# DB10005_CellNode.net
KiCad netlist of a schematic drawn in Altium Designer
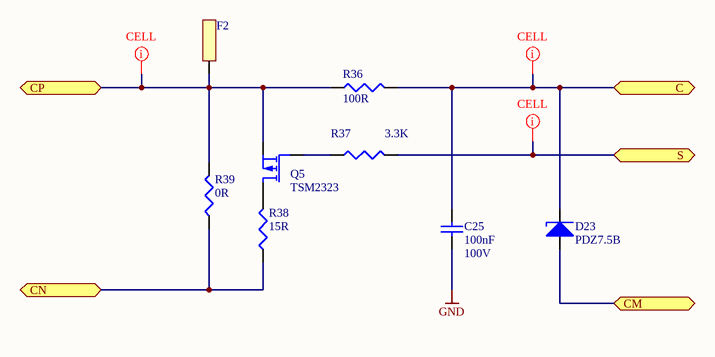
[diagram p0: DB10005_CellNode.SchDoc]

(export (version "E")
  (design (tool "Eeschema 10.0.6"))
  (components
    (comp (ref "C25")
      (value "100nF")
      (footprint "C-0805")
      (description "Capacitor, 100nF, 100V, X7R")
      (fields (field (name "VOLTAGE RATING") "100V"))
      (libsource (lib "AR_Capacitors_Ceramic") (part "100nF/0805/CER/100V"))
    )
    (comp (ref "D23")
      (value "PDZ7.5B")
      (footprint "SOD-323")
      (description "Diode, Vrrm: 7.5V, If: 0.2A, Vf: 0.9V")
      (libsource (lib "AR_Diodes") (part "PDZ7.5B"))
    )
    (comp (ref "F2")
      (value "PCB Fuse")
      (footprint "0603_Fuse_0_2MM")
      (description "Fuse, PCB, 1A, 60V, T:-40°C +85°C")
      (libsource (lib "AR_Misc") (part "PCBFuse_0_2MM"))
    )
    (comp (ref "Q5")
      (value "TSM2323")
      (footprint "SOT-23")
      (description "Mosfet, P-channel, Vds:20V, Id:4.7A, Vgs-th:1V, Rds-on:0.039ohm")
      (libsource (lib "AR_Mosfets") (part "TSM2323"))
    )
    (comp (ref "R36")
      (value "100R")
      (footprint "0603")
      (description "Resistor, 100R, 1%, 0.063W, 50V, 200PPM, 0603")
      (libsource (lib "AR_Resistors_SMD") (part "100/0603/0063W/50V"))
    )
    (comp (ref "R37")
      (value "3.3K")
      (footprint "0603")
      (description "Resistor, 3.3K, 1%, 0.125W, 50V, 100PPM, 0603")
      (libsource (lib "AR_Resistors_SMD") (part "3.3K/0603/0125W/50V"))
    )
    (comp (ref "R38")
      (value "15R")
      (footprint "2512")
      (description "Resistor, 15R, 1%, 2W, 200V, 200PPM, 2512")
      (libsource (lib "AR_Resistors_SMD") (part "15/2512/2W/250V"))
    )
    (comp (ref "R39")
      (value "0R")
      (footprint "0805")
      (description "Resistor, 0R, 0.1%, 0.1W, 150V, 200PPM, 0805")
      (libsource (lib "AR_Resistors_SMD") (part "0/0805/0100W/150V"))
    )
  )
  (nets
    (net (code "1") (name "/C") (class "Default")
      (node (ref "C25") (pin "2") (pinfunction "2_2") (pintype "passive"))
      (node (ref "D23") (pin "2") (pinfunction "2_2") (pintype "passive"))
      (node (ref "R36") (pin "2") (pinfunction "2_2") (pintype "passive"))
    )
    (net (code "2") (name "/CM") (class "Default")
      (node (ref "D23") (pin "1") (pinfunction "1_1") (pintype "passive"))
    )
    (net (code "3") (name "/CN") (class "Default")
      (node (ref "R38") (pin "1") (pinfunction "1_1") (pintype "passive"))
      (node (ref "R39") (pin "1") (pinfunction "1_1") (pintype "passive"))
    )
    (net (code "4") (name "/CP") (class "Default")
      (node (ref "F2") (pin "1") (pinfunction "1_1") (pintype "passive"))
      (node (ref "Q5") (pin "S") (pinfunction "S_S") (pintype "passive"))
      (node (ref "R36") (pin "1") (pinfunction "1_1") (pintype "passive"))
      (node (ref "R39") (pin "2") (pinfunction "2_2") (pintype "passive"))
    )
    (net (code "5") (name "/S") (class "Default")
      (node (ref "R37") (pin "2") (pinfunction "2_2") (pintype "passive"))
    )
    (net (code "6") (name "GND") (class "Default")
      (node (ref "C25") (pin "1") (pinfunction "1_1") (pintype "passive"))
    )
    (net (code "7") (name "Net-(Q5-PadD)") (class "Default")
      (node (ref "Q5") (pin "D") (pinfunction "D_D") (pintype "passive"))
      (node (ref "R38") (pin "2") (pinfunction "2_2") (pintype "passive"))
    )
    (net (code "8") (name "Net-(Q5-PadG)") (class "Default")
      (node (ref "Q5") (pin "G") (pinfunction "G_G") (pintype "passive"))
      (node (ref "R37") (pin "1") (pinfunction "1_1") (pintype "passive"))
    )
  )
)
